# ProPrj_HSSM-Prog_2025-06-12.net
KiCad netlist of a schematic drawn in EasyEDA Pro
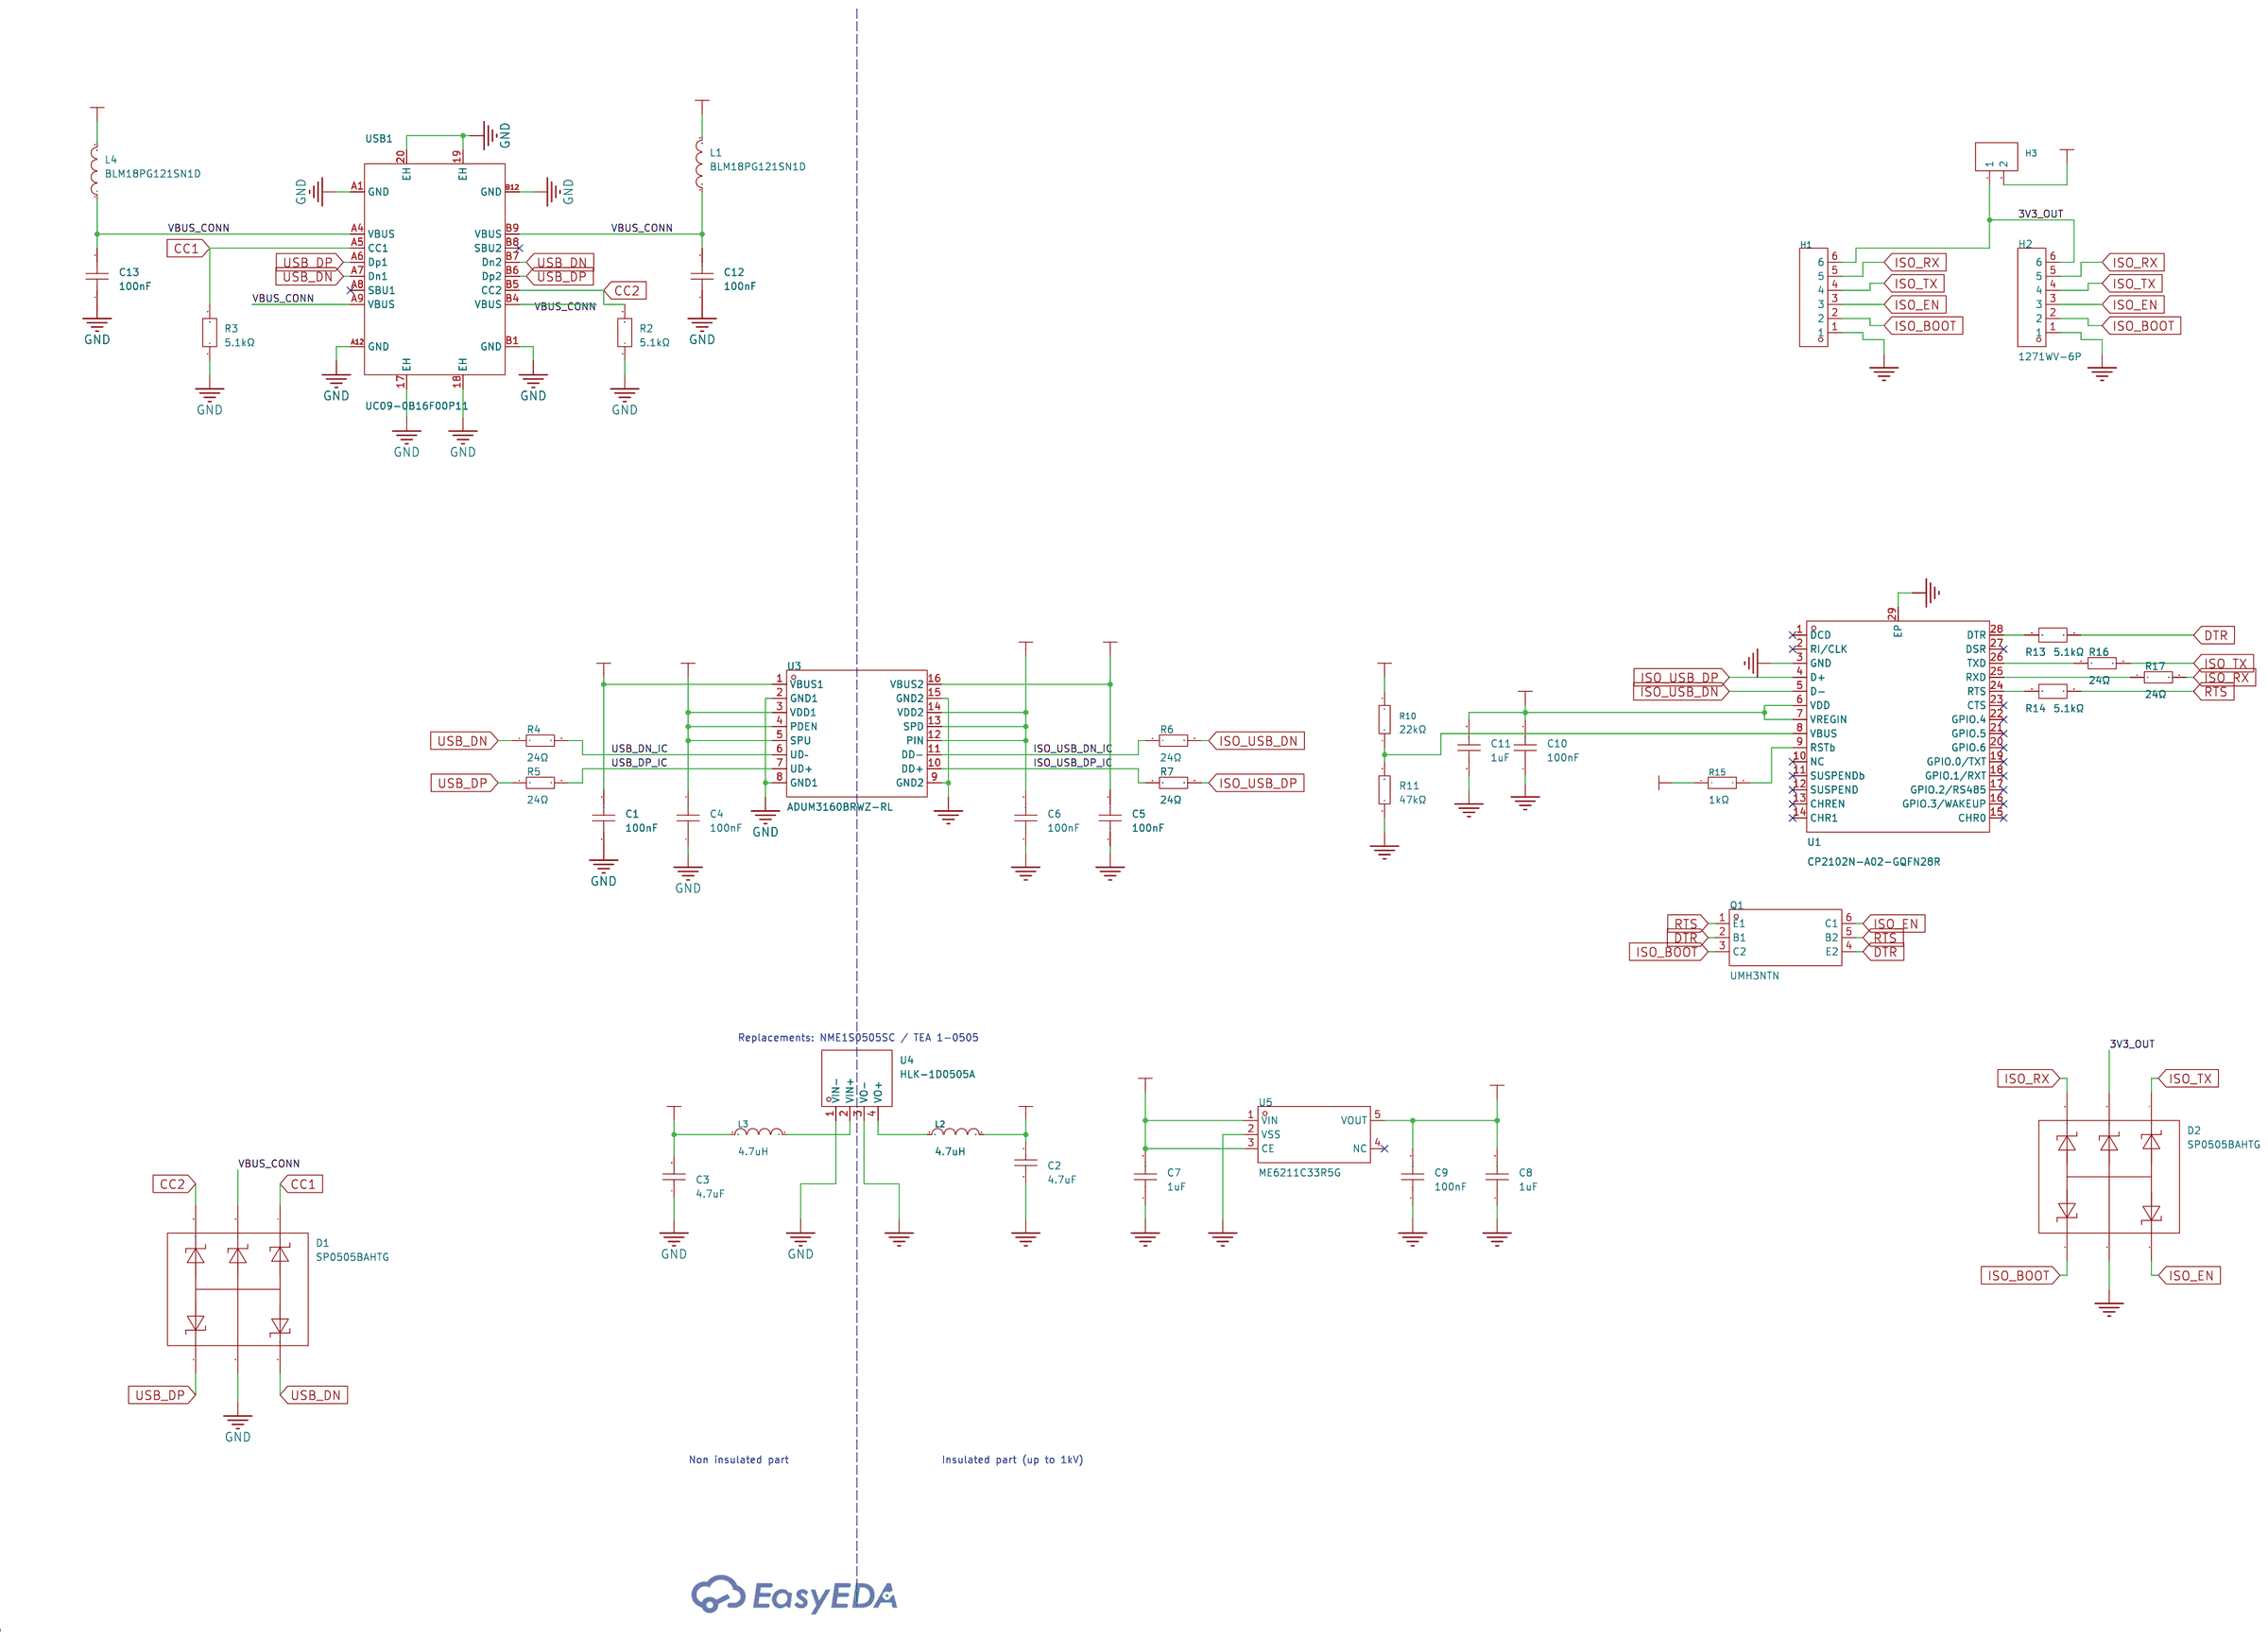
[diagram p0: schematic sheet]

(export (version "E")
  (design (tool "Eeschema 10.0.6"))
  (components
    (comp (ref "C1")
      (value "100nF")
      (footprint "easyedapro:C0402")
      (fields
        (field (name "Manufacturer Part") "CL05B104KO5NNNC")
        (field (name "Manufacturer") "SAMSUNG(三星)")
      )
      (libsource (lib "easyedapro") (part "CL05B104KO5NNNC"))
    )
    (comp (ref "C2")
      (value "4.7uF")
      (footprint "easyedapro:C0603")
      (fields
        (field (name "Manufacturer Part") "CL10A475KO8NNNC")
        (field (name "Manufacturer") "SAMSUNG(三星)")
      )
      (libsource (lib "easyedapro") (part "CL10A475KO8NNNC"))
    )
    (comp (ref "C3")
      (value "4.7uF")
      (footprint "easyedapro:C0603")
      (fields
        (field (name "Manufacturer Part") "CL10A475KO8NNNC")
        (field (name "Manufacturer") "SAMSUNG(三星)")
      )
      (libsource (lib "easyedapro") (part "CL10A475KO8NNNC"))
    )
    (comp (ref "C4")
      (value "100nF")
      (footprint "easyedapro:C0402")
      (fields
        (field (name "Manufacturer Part") "CL05B104KO5NNNC")
        (field (name "Manufacturer") "SAMSUNG(三星)")
      )
      (libsource (lib "easyedapro") (part "CL05B104KO5NNNC"))
    )
    (comp (ref "C5")
      (value "100nF")
      (footprint "easyedapro:C0402")
      (fields
        (field (name "Manufacturer Part") "CL05B104KO5NNNC")
        (field (name "Manufacturer") "SAMSUNG(三星)")
      )
      (libsource (lib "easyedapro") (part "CL05B104KO5NNNC"))
    )
    (comp (ref "C6")
      (value "100nF")
      (footprint "easyedapro:C0402")
      (fields
        (field (name "Manufacturer Part") "CL05B104KO5NNNC")
        (field (name "Manufacturer") "SAMSUNG(三星)")
      )
      (libsource (lib "easyedapro") (part "CL05B104KO5NNNC"))
    )
    (comp (ref "C7")
      (value "1uF")
      (footprint "easyedapro:C0402")
      (fields
        (field (name "Manufacturer Part") "CL05A105KA5NQNC")
        (field (name "Manufacturer") "SAMSUNG(三星)")
      )
      (libsource (lib "easyedapro") (part "CL05A105KA5NQNC"))
    )
    (comp (ref "C8")
      (value "1uF")
      (footprint "easyedapro:C0402")
      (fields
        (field (name "Manufacturer Part") "CL05A105KA5NQNC")
        (field (name "Manufacturer") "SAMSUNG(三星)")
      )
      (libsource (lib "easyedapro") (part "CL05A105KA5NQNC"))
    )
    (comp (ref "C9")
      (value "100nF")
      (footprint "easyedapro:C0402")
      (fields
        (field (name "Manufacturer Part") "CL05B104KO5NNNC")
        (field (name "Manufacturer") "SAMSUNG(三星)")
      )
      (libsource (lib "easyedapro") (part "CL05B104KO5NNNC"))
    )
    (comp (ref "C10")
      (value "100nF")
      (footprint "easyedapro:C0402")
      (fields
        (field (name "Manufacturer Part") "CL05B104KO5NNNC")
        (field (name "Manufacturer") "SAMSUNG(三星)")
      )
      (libsource (lib "easyedapro") (part "CL05B104KO5NNNC"))
    )
    (comp (ref "C11")
      (value "1uF")
      (footprint "easyedapro:C0402")
      (fields
        (field (name "Manufacturer Part") "CL05A105KA5NQNC")
        (field (name "Manufacturer") "SAMSUNG(三星)")
      )
      (libsource (lib "easyedapro") (part "CL05A105KA5NQNC"))
    )
    (comp (ref "C12")
      (value "100nF")
      (footprint "easyedapro:C0402")
      (fields
        (field (name "Manufacturer Part") "CL05B104KO5NNNC")
        (field (name "Manufacturer") "SAMSUNG(三星)")
      )
      (libsource (lib "easyedapro") (part "CL05B104KO5NNNC"))
    )
    (comp (ref "C13")
      (value "100nF")
      (footprint "easyedapro:C0402")
      (fields
        (field (name "Manufacturer Part") "CL05B104KO5NNNC")
        (field (name "Manufacturer") "SAMSUNG(三星)")
      )
      (libsource (lib "easyedapro") (part "CL05B104KO5NNNC"))
    )
    (comp (ref "D1")
      (value "SP0505BAHTG")
      (footprint "easyedapro:SOT-23-6_L2.9-W1.6-P0.95-LS2.8-BR")
      (fields (field (name "Manufacturer") "Littelfuse(美国力特)"))
      (libsource (lib "easyedapro") (part "SP0505BAHTG"))
    )
    (comp (ref "D2")
      (value "SP0505BAHTG")
      (footprint "easyedapro:SOT-23-6_L2.9-W1.6-P0.95-LS2.8-BR")
      (fields (field (name "Manufacturer") "Littelfuse(美国力特)"))
      (libsource (lib "easyedapro") (part "SP0505BAHTG"))
    )
    (comp (ref "H1")
      (value "~")
      (footprint "easyedapro:HDR-TH_6P-P2.54-V-F")
      (libsource (lib "easyedapro") (part "Header-Female-2.54_1x6"))
    )
    (comp (ref "H2")
      (value "1271WV-6P")
      (footprint "easyedapro:HDR-TH_6P-P1.27-V-M-A")
      (fields (field (name "Manufacturer") "HanElectricity(瀚源)"))
      (libsource (lib "easyedapro") (part "1271WV-6P"))
    )
    (comp (ref "H3")
      (value "~")
      (footprint "easyedapro:HDR-TH_2P-P2.54-V-F")
      (libsource (lib "easyedapro") (part "Header-Female-2.54_1x2"))
    )
    (comp (ref "L1")
      (value "BLM18PG121SN1D")
      (footprint "easyedapro:L0603")
      (fields (field (name "Manufacturer") "muRata(村田)"))
      (libsource (lib "easyedapro") (part "BLM18PG121SN1D_C14709"))
    )
    (comp (ref "L2")
      (value "4.7uH")
      (footprint "easyedapro:IND-SMD_L4.0-W4.0_SMNR4020")
      (fields (field (name "Manufacturer Part") "FNR4012S4R7MT") (field (name "Manufacturer") "cjiang(长江微电)"))
      (libsource (lib "easyedapro") (part "FNR4012S4R7MT"))
    )
    (comp (ref "L3")
      (value "4.7uH")
      (footprint "easyedapro:IND-SMD_L4.0-W4.0_SMNR4020")
      (fields (field (name "Manufacturer Part") "FNR4012S4R7MT") (field (name "Manufacturer") "cjiang(长江微电)"))
      (libsource (lib "easyedapro") (part "FNR4012S4R7MT"))
    )
    (comp (ref "L4")
      (value "BLM18PG121SN1D")
      (footprint "easyedapro:L0603")
      (fields (field (name "Manufacturer") "muRata(村田)"))
      (libsource (lib "easyedapro") (part "BLM18PG121SN1D_C14709"))
    )
    (comp (ref "Q1")
      (value "UMH3NTN")
      (footprint "easyedapro:SOT-363_L2.0-W1.3-P0.65-LS2.1-TL")
      (fields (field (name "Manufacturer") "ROHM(罗姆)"))
      (libsource (lib "easyedapro") (part "UMH3NTN"))
    )
    (comp (ref "R2")
      (value "5.1kΩ")
      (footprint "easyedapro:R0402")
      (fields (field (name "Manufacturer Part") "RCA025K1JLF") (field (name "Manufacturer") "HKR(香港电阻)"))
      (libsource (lib "easyedapro") (part "RCA025K1JLF"))
    )
    (comp (ref "R3")
      (value "5.1kΩ")
      (footprint "easyedapro:R0402")
      (fields (field (name "Manufacturer Part") "RCA025K1JLF") (field (name "Manufacturer") "HKR(香港电阻)"))
      (libsource (lib "easyedapro") (part "RCA025K1JLF"))
    )
    (comp (ref "R4")
      (value "24Ω")
      (footprint "easyedapro:R0402")
      (fields (field (name "Manufacturer Part") "AC0402FR-0724RL") (field (name "Manufacturer") "YAGEO(国巨)"))
      (libsource (lib "easyedapro") (part "AC0402FR-0724RL"))
    )
    (comp (ref "R5")
      (value "24Ω")
      (footprint "easyedapro:R0402")
      (fields (field (name "Manufacturer Part") "AC0402FR-0724RL") (field (name "Manufacturer") "YAGEO(国巨)"))
      (libsource (lib "easyedapro") (part "AC0402FR-0724RL"))
    )
    (comp (ref "R6")
      (value "24Ω")
      (footprint "easyedapro:R0402")
      (fields (field (name "Manufacturer Part") "AC0402FR-0724RL") (field (name "Manufacturer") "YAGEO(国巨)"))
      (libsource (lib "easyedapro") (part "AC0402FR-0724RL"))
    )
    (comp (ref "R7")
      (value "24Ω")
      (footprint "easyedapro:R0402")
      (fields (field (name "Manufacturer Part") "AC0402FR-0724RL") (field (name "Manufacturer") "YAGEO(国巨)"))
      (libsource (lib "easyedapro") (part "AC0402FR-0724RL"))
    )
    (comp (ref "R10")
      (value "22kΩ")
      (footprint "easyedapro:R0402")
      (fields
        (field (name "Manufacturer Part") "0402WGF2202TCE")
        (field (name "Manufacturer") "UNI-ROYAL(厚声)")
      )
      (libsource (lib "easyedapro") (part "0402WGF2202TCE"))
    )
    (comp (ref "R11")
      (value "47kΩ")
      (footprint "easyedapro:R0402")
      (fields
        (field (name "Manufacturer Part") "0402WGF4702TCE")
        (field (name "Manufacturer") "UNI-ROYAL(厚声)")
      )
      (libsource (lib "easyedapro") (part "0402WGF4702TCE"))
    )
    (comp (ref "R13")
      (value "5.1kΩ")
      (footprint "easyedapro:R0402")
      (fields (field (name "Manufacturer Part") "RCA025K1JLF") (field (name "Manufacturer") "HKR(香港电阻)"))
      (libsource (lib "easyedapro") (part "RCA025K1JLF"))
    )
    (comp (ref "R14")
      (value "5.1kΩ")
      (footprint "easyedapro:R0402")
      (fields (field (name "Manufacturer Part") "RCA025K1JLF") (field (name "Manufacturer") "HKR(香港电阻)"))
      (libsource (lib "easyedapro") (part "RCA025K1JLF"))
    )
    (comp (ref "R15")
      (value "1kΩ")
      (footprint "easyedapro:R0402")
      (fields
        (field (name "Manufacturer Part") "0402WGF1001TCE")
        (field (name "Manufacturer") "UNI-ROYAL(厚声)")
      )
      (libsource (lib "easyedapro") (part "0402WGF1001TCE"))
    )
    (comp (ref "R16")
      (value "24Ω")
      (footprint "easyedapro:R0402")
      (fields (field (name "Manufacturer Part") "AC0402FR-0724RL") (field (name "Manufacturer") "YAGEO(国巨)"))
      (libsource (lib "easyedapro") (part "AC0402FR-0724RL"))
    )
    (comp (ref "R17")
      (value "24Ω")
      (footprint "easyedapro:R0402")
      (fields (field (name "Manufacturer Part") "AC0402FR-0724RL") (field (name "Manufacturer") "YAGEO(国巨)"))
      (libsource (lib "easyedapro") (part "AC0402FR-0724RL"))
    )
    (comp (ref "U1")
      (value "CP2102N-A02-GQFN28R")
      (footprint "easyedapro:QFN-28_L5.0-W5.0-P0.50-TL-EP3.3")
      (fields (field (name "Manufacturer") "SKYWORKS/SILICON LABS(芯科)"))
      (libsource (lib "easyedapro") (part "CP2102N-A02-GQFN28R"))
    )
    (comp (ref "U3")
      (value "ADUM3160BRWZ-RL")
      (footprint "easyedapro:SOIC-16_L10.3-W7.5-P1.27-LS10.3-BL")
      (fields (field (name "Manufacturer") "ADI(亚德诺)"))
      (libsource (lib "easyedapro") (part "ADUM3160BRWZ-RL"))
    )
    (comp (ref "U4")
      (value "HLK-1D0505A")
      (footprint "easyedapro:PWRM-TH_HLK-1DXXXX")
      (fields (field (name "Manufacturer") "HI-LINK(海凌科)"))
      (libsource (lib "easyedapro") (part "HLK-1D0505A"))
    )
    (comp (ref "U5")
      (value "ME6211C33R5G")
      (footprint "easyedapro:SOT-353_L2.1-W1.3-P0.65-LS2.3-BL")
      (fields (field (name "Manufacturer") "MICRONE(南京微盟)"))
      (libsource (lib "easyedapro") (part "ME6211C33R5G"))
    )
    (comp (ref "USB1")
      (value "UC09-0B16F00P11")
      (footprint "easyedapro:USB-C_UC09-0B16F00P11")
      (fields (field (name "Manufacturer") "BXCONN(宝讯)"))
      (libsource (lib "easyedapro") (part "UC09-0B16F00P11"))
    )
  )
  (nets
    (net (code "1") (name "/3V3_OUT") (class "Default")
      (node (ref "D2") (pin "5") (pinfunction "5_5") (pintype "input"))
      (node (ref "H1") (pin "6") (pinfunction "6_6") (pintype "input"))
      (node (ref "H2") (pin "6") (pinfunction "6_6") (pintype "unspecified"))
      (node (ref "H3") (pin "1") (pinfunction "1_1") (pintype "input"))
    )
    (net (code "2") (name "/ISO_USB_DN_IC") (class "Default")
      (node (ref "R6") (pin "1") (pinfunction "1_1") (pintype "unspecified"))
      (node (ref "U3") (pin "11") (pinfunction "DD-_11") (pintype "unspecified"))
    )
    (net (code "3") (name "/ISO_USB_DP_IC") (class "Default")
      (node (ref "R7") (pin "1") (pinfunction "1_1") (pintype "unspecified"))
      (node (ref "U3") (pin "10") (pinfunction "DD+_10") (pintype "unspecified"))
    )
    (net (code "4") (name "/USB_DN_IC") (class "Default")
      (node (ref "R4") (pin "2") (pinfunction "2_2") (pintype "unspecified"))
      (node (ref "U3") (pin "6") (pinfunction "UD–_6") (pintype "unspecified"))
    )
    (net (code "5") (name "/USB_DP_IC") (class "Default")
      (node (ref "R5") (pin "2") (pinfunction "2_2") (pintype "unspecified"))
      (node (ref "U3") (pin "7") (pinfunction "UD+_7") (pintype "unspecified"))
    )
    (net (code "6") (name "/VBUS_CONN") (class "Default")
      (node (ref "C12") (pin "2") (pinfunction "2_2") (pintype "unspecified"))
      (node (ref "C13") (pin "2") (pinfunction "2_2") (pintype "unspecified"))
      (node (ref "D1") (pin "5") (pinfunction "5_5") (pintype "input"))
      (node (ref "L1") (pin "1") (pinfunction "1_1") (pintype "unspecified"))
      (node (ref "L4") (pin "1") (pinfunction "1_1") (pintype "unspecified"))
      (node (ref "USB1") (pin "A4") (pinfunction "VBUS_A4") (pintype "unspecified"))
      (node (ref "USB1") (pin "A9") (pinfunction "VBUS_A9") (pintype "unspecified"))
      (node (ref "USB1") (pin "B4") (pinfunction "VBUS_B4") (pintype "unspecified"))
      (node (ref "USB1") (pin "B9") (pinfunction "VBUS_B9") (pintype "unspecified"))
    )
    (net (code "7") (name "CC1") (class "Default")
      (node (ref "D1") (pin "4") (pinfunction "4_4") (pintype "input"))
      (node (ref "R3") (pin "2") (pinfunction "2_2") (pintype "unspecified"))
      (node (ref "USB1") (pin "A5") (pinfunction "CC1_A5") (pintype "unspecified"))
    )
    (net (code "8") (name "CC2") (class "Default")
      (node (ref "D1") (pin "6") (pinfunction "6_6") (pintype "input"))
      (node (ref "R2") (pin "2") (pinfunction "2_2") (pintype "unspecified"))
      (node (ref "USB1") (pin "B5") (pinfunction "CC2_B5") (pintype "unspecified"))
    )
    (net (code "9") (name "DTR") (class "Default")
      (node (ref "Q1") (pin "2") (pinfunction "B1_2") (pintype "unspecified"))
      (node (ref "Q1") (pin "4") (pinfunction "E2_4") (pintype "unspecified"))
      (node (ref "R13") (pin "1") (pinfunction "1_1") (pintype "unspecified"))
    )
    (net (code "10") (name "GND") (class "Default")
      (node (ref "C1") (pin "1") (pinfunction "1_1") (pintype "unspecified"))
      (node (ref "C12") (pin "1") (pinfunction "1_1") (pintype "unspecified"))
      (node (ref "C13") (pin "1") (pinfunction "1_1") (pintype "unspecified"))
      (node (ref "C3") (pin "1") (pinfunction "1_1") (pintype "input"))
      (node (ref "C4") (pin "1") (pinfunction "1_1") (pintype "unspecified"))
      (node (ref "D1") (pin "2") (pinfunction "2_2") (pintype "input"))
      (node (ref "R2") (pin "1") (pinfunction "1_1") (pintype "unspecified"))
      (node (ref "R3") (pin "1") (pinfunction "1_1") (pintype "unspecified"))
      (node (ref "U3") (pin "2") (pinfunction "GND1_2") (pintype "unspecified"))
      (node (ref "U3") (pin "8") (pinfunction "GND1_8") (pintype "unspecified"))
      (node (ref "U4") (pin "1") (pinfunction "VIN-_1") (pintype "unspecified"))
      (node (ref "USB1") (pin "17") (pinfunction "EH_17") (pintype "unspecified"))
      (node (ref "USB1") (pin "18") (pinfunction "EH_18") (pintype "unspecified"))
      (node (ref "USB1") (pin "19") (pinfunction "EH_19") (pintype "unspecified"))
      (node (ref "USB1") (pin "20") (pinfunction "EH_20") (pintype "unspecified"))
      (node (ref "USB1") (pin "A1") (pinfunction "GND_A1") (pintype "unspecified"))
      (node (ref "USB1") (pin "A12") (pinfunction "GND_A12") (pintype "unspecified"))
      (node (ref "USB1") (pin "B1") (pinfunction "GND_B1") (pintype "unspecified"))
      (node (ref "USB1") (pin "B12") (pinfunction "GND_B12") (pintype "unspecified"))
    )
    (net (code "11") (name "ISO3V3") (class "Default")
      (node (ref "C10") (pin "2") (pinfunction "2_2") (pintype "unspecified"))
      (node (ref "C11") (pin "2") (pinfunction "2_2") (pintype "unspecified"))
      (node (ref "C8") (pin "2") (pinfunction "2_2") (pintype "unspecified"))
      (node (ref "C9") (pin "2") (pinfunction "2_2") (pintype "unspecified"))
      (node (ref "H3") (pin "2") (pinfunction "2_2") (pintype "input"))
      (node (ref "R15") (pin "1") (pinfunction "1_1") (pintype "input"))
      (node (ref "U1") (pin "6") (pinfunction "VDD_6") (pintype "unspecified"))
      (node (ref "U1") (pin "7") (pinfunction "VREGIN_7") (pintype "unspecified"))
      (node (ref "U5") (pin "5") (pinfunction "VOUT_5") (pintype "input"))
    )
    (net (code "12") (name "ISOGND") (class "Default")
      (node (ref "C10") (pin "1") (pinfunction "1_1") (pintype "unspecified"))
      (node (ref "C11") (pin "1") (pinfunction "1_1") (pintype "unspecified"))
      (node (ref "C2") (pin "1") (pinfunction "1_1") (pintype "input"))
      (node (ref "C5") (pin "1") (pinfunction "1_1") (pintype "unspecified"))
      (node (ref "C6") (pin "1") (pinfunction "1_1") (pintype "unspecified"))
      (node (ref "C7") (pin "1") (pinfunction "1_1") (pintype "unspecified"))
      (node (ref "C8") (pin "1") (pinfunction "1_1") (pintype "unspecified"))
      (node (ref "C9") (pin "1") (pinfunction "1_1") (pintype "unspecified"))
      (node (ref "D2") (pin "2") (pinfunction "2_2") (pintype "input"))
      (node (ref "H1") (pin "1") (pinfunction "1_1") (pintype "input"))
      (node (ref "H2") (pin "1") (pinfunction "1_1") (pintype "unspecified"))
      (node (ref "R11") (pin "1") (pinfunction "1_1") (pintype "input"))
      (node (ref "U1") (pin "29") (pinfunction "EP_29") (pintype "unspecified"))
      (node (ref "U1") (pin "3") (pinfunction "GND_3") (pintype "unspecified"))
      (node (ref "U3") (pin "15") (pinfunction "GND2_15") (pintype "unspecified"))
      (node (ref "U3") (pin "9") (pinfunction "GND2_9") (pintype "unspecified"))
      (node (ref "U4") (pin "3") (pinfunction "VO-_3") (pintype "unspecified"))
      (node (ref "U5") (pin "2") (pinfunction "VSS_2") (pintype "input"))
    )
    (net (code "13") (name "ISOVBUS") (class "Default")
      (node (ref "C2") (pin "2") (pinfunction "2_2") (pintype "input"))
      (node (ref "C5") (pin "2") (pinfunction "2_2") (pintype "unspecified"))
      (node (ref "C7") (pin "2") (pinfunction "2_2") (pintype "unspecified"))
      (node (ref "L2") (pin "1") (pinfunction "1_1") (pintype "input"))
      (node (ref "R10") (pin "2") (pinfunction "2_2") (pintype "input"))
      (node (ref "U3") (pin "16") (pinfunction "VBUS2_16") (pintype "unspecified"))
      (node (ref "U5") (pin "1") (pinfunction "VIN_1") (pintype "input"))
      (node (ref "U5") (pin "3") (pinfunction "CE_3") (pintype "input"))
    )
    (net (code "14") (name "ISOVDD") (class "Default")
      (node (ref "C6") (pin "2") (pinfunction "2_2") (pintype "unspecified"))
      (node (ref "U3") (pin "12") (pinfunction "PIN_12") (pintype "unspecified"))
      (node (ref "U3") (pin "13") (pinfunction "SPD_13") (pintype "unspecified"))
      (node (ref "U3") (pin "14") (pinfunction "VDD2_14") (pintype "unspecified"))
    )
    (net (code "15") (name "ISO_BOOT") (class "Default")
      (node (ref "D2") (pin "1") (pinfunction "1_1") (pintype "input"))
      (node (ref "H1") (pin "2") (pinfunction "2_2") (pintype "input"))
      (node (ref "H2") (pin "2") (pinfunction "2_2") (pintype "unspecified"))
      (node (ref "Q1") (pin "3") (pinfunction "C2_3") (pintype "unspecified"))
    )
    (net (code "16") (name "ISO_EN") (class "Default")
      (node (ref "D2") (pin "3") (pinfunction "3_3") (pintype "input"))
      (node (ref "H1") (pin "3") (pinfunction "3_3") (pintype "input"))
      (node (ref "H2") (pin "3") (pinfunction "3_3") (pintype "unspecified"))
      (node (ref "Q1") (pin "6") (pinfunction "C1_6") (pintype "unspecified"))
    )
    (net (code "17") (name "ISO_RX") (class "Default")
      (node (ref "D2") (pin "6") (pinfunction "6_6") (pintype "input"))
      (node (ref "H1") (pin "5") (pinfunction "5_5") (pintype "input"))
      (node (ref "H2") (pin "5") (pinfunction "5_5") (pintype "unspecified"))
      (node (ref "R17") (pin "2") (pinfunction "2_2") (pintype "unspecified"))
    )
    (net (code "18") (name "ISO_TX") (class "Default")
      (node (ref "D2") (pin "4") (pinfunction "4_4") (pintype "input"))
      (node (ref "H1") (pin "4") (pinfunction "4_4") (pintype "input"))
      (node (ref "H2") (pin "4") (pinfunction "4_4") (pintype "unspecified"))
      (node (ref "R16") (pin "2") (pinfunction "2_2") (pintype "unspecified"))
    )
    (net (code "19") (name "ISO_USB_DN") (class "Default")
      (node (ref "R6") (pin "2") (pinfunction "2_2") (pintype "unspecified"))
      (node (ref "U1") (pin "5") (pinfunction "D-_5") (pintype "unspecified"))
    )
    (net (code "20") (name "ISO_USB_DP") (class "Default")
      (node (ref "R7") (pin "2") (pinfunction "2_2") (pintype "unspecified"))
      (node (ref "U1") (pin "4") (pinfunction "D+_4") (pintype "unspecified"))
    )
    (net (code "21") (name "Net-(U1-DTR)") (class "Default")
      (node (ref "R13") (pin "2") (pinfunction "2_2") (pintype "unspecified"))
      (node (ref "U1") (pin "28") (pinfunction "DTR_28") (pintype "unspecified"))
    )
    (net (code "22") (name "Net-(U1-RSTb)") (class "Default")
      (node (ref "R15") (pin "2") (pinfunction "2_2") (pintype "input"))
      (node (ref "U1") (pin "9") (pinfunction "RSTb_9") (pintype "unspecified"))
    )
    (net (code "23") (name "Net-(U1-RTS)") (class "Default")
      (node (ref "R14") (pin "2") (pinfunction "2_2") (pintype "unspecified"))
      (node (ref "U1") (pin "24") (pinfunction "RTS_24") (pintype "unspecified"))
    )
    (net (code "24") (name "Net-(U1-RXD)") (class "Default")
      (node (ref "R17") (pin "1") (pinfunction "1_1") (pintype "unspecified"))
      (node (ref "U1") (pin "25") (pinfunction "RXD_25") (pintype "unspecified"))
    )
    (net (code "25") (name "Net-(U1-TXD)") (class "Default")
      (node (ref "R16") (pin "1") (pinfunction "1_1") (pintype "unspecified"))
      (node (ref "U1") (pin "26") (pinfunction "TXD_26") (pintype "unspecified"))
    )
    (net (code "26") (name "Net-(U1-VBUS)") (class "Default")
      (node (ref "R10") (pin "1") (pinfunction "1_1") (pintype "input"))
      (node (ref "R11") (pin "2") (pinfunction "2_2") (pintype "input"))
      (node (ref "U1") (pin "8") (pinfunction "VBUS_8") (pintype "unspecified"))
    )
    (net (code "27") (name "Net-(U4-VIN+)") (class "Default")
      (node (ref "L3") (pin "1") (pinfunction "1_1") (pintype "input"))
      (node (ref "U4") (pin "2") (pinfunction "VIN+_2") (pintype "unspecified"))
    )
    (net (code "28") (name "Net-(U4-VO+)") (class "Default")
      (node (ref "L2") (pin "2") (pinfunction "2_2") (pintype "input"))
      (node (ref "U4") (pin "4") (pinfunction "VO+_4") (pintype "unspecified"))
    )
    (net (code "29") (name "RTS") (class "Default")
      (node (ref "Q1") (pin "1") (pinfunction "E1_1") (pintype "unspecified"))
      (node (ref "Q1") (pin "5") (pinfunction "B2_5") (pintype "unspecified"))
      (node (ref "R14") (pin "1") (pinfunction "1_1") (pintype "unspecified"))
    )
    (net (code "30") (name "USB_DN") (class "Default")
      (node (ref "D1") (pin "3") (pinfunction "3_3") (pintype "input"))
      (node (ref "R4") (pin "1") (pinfunction "1_1") (pintype "unspecified"))
      (node (ref "USB1") (pin "A7") (pinfunction "Dn1_A7") (pintype "unspecified"))
      (node (ref "USB1") (pin "B7") (pinfunction "Dn2_B7") (pintype "unspecified"))
    )
    (net (code "31") (name "USB_DP") (class "Default")
      (node (ref "D1") (pin "1") (pinfunction "1_1") (pintype "input"))
      (node (ref "R5") (pin "1") (pinfunction "1_1") (pintype "unspecified"))
      (node (ref "USB1") (pin "A6") (pinfunction "Dp1_A6") (pintype "unspecified"))
      (node (ref "USB1") (pin "B6") (pinfunction "Dp2_B6") (pintype "unspecified"))
    )
    (net (code "32") (name "VBUS") (class "Default")
      (node (ref "C1") (pin "2") (pinfunction "2_2") (pintype "unspecified"))
      (node (ref "C3") (pin "2") (pinfunction "2_2") (pintype "input"))
      (node (ref "L1") (pin "2") (pinfunction "2_2") (pintype "unspecified"))
      (node (ref "L3") (pin "2") (pinfunction "2_2") (pintype "input"))
      (node (ref "L4") (pin "2") (pinfunction "2_2") (pintype "unspecified"))
      (node (ref "U3") (pin "1") (pinfunction "VBUS1_1") (pintype "unspecified"))
    )
    (net (code "33") (name "VDD") (class "Default")
      (node (ref "C4") (pin "2") (pinfunction "2_2") (pintype "unspecified"))
      (node (ref "U3") (pin "3") (pinfunction "VDD1_3") (pintype "unspecified"))
      (node (ref "U3") (pin "4") (pinfunction "PDEN_4") (pintype "unspecified"))
      (node (ref "U3") (pin "5") (pinfunction "SPU_5") (pintype "unspecified"))
    )
    (net (code "34") (name "unconnected-(U1-CHR0-Pad15)") (class "Default")
      (node (ref "U1") (pin "15") (pinfunction "CHR0_15") (pintype "unspecified+no_connect"))
    )
    (net (code "35") (name "unconnected-(U1-CHR1-Pad14)") (class "Default")
      (node (ref "U1") (pin "14") (pinfunction "CHR1_14") (pintype "unspecified+no_connect"))
    )
    (net (code "36") (name "unconnected-(U1-CHREN-Pad13)") (class "Default")
      (node (ref "U1") (pin "13") (pinfunction "CHREN_13") (pintype "unspecified+no_connect"))
    )
    (net (code "37") (name "unconnected-(U1-CTS-Pad23)") (class "Default")
      (node (ref "U1") (pin "23") (pinfunction "CTS_23") (pintype "unspecified+no_connect"))
    )
    (net (code "38") (name "unconnected-(U1-DCD-Pad1)") (class "Default")
      (node (ref "U1") (pin "1") (pinfunction "DCD_1") (pintype "unspecified+no_connect"))
    )
    (net (code "39") (name "unconnected-(U1-DSR-Pad27)") (class "Default")
      (node (ref "U1") (pin "27") (pinfunction "DSR_27") (pintype "unspecified+no_connect"))
    )
    (net (code "40") (name "unconnected-(U1-GPIO.0{slash}TXT-Pad19)") (class "Default")
      (node (ref "U1") (pin "19") (pinfunction "GPIO.0/TXT_19") (pintype "unspecified+no_connect"))
    )
    (net (code "41") (name "unconnected-(U1-GPIO.1{slash}RXT-Pad18)") (class "Default")
      (node (ref "U1") (pin "18") (pinfunction "GPIO.1/RXT_18") (pintype "unspecified+no_connect"))
    )
    (net (code "42") (name "unconnected-(U1-GPIO.2{slash}RS485-Pad17)") (class "Default")
      (node (ref "U1") (pin "17") (pinfunction "GPIO.2/RS485_17") (pintype "unspecified+no_connect"))
    )
    (net (code "43") (name "unconnected-(U1-GPIO.3{slash}WAKEUP-Pad16)") (class "Default")
      (node (ref "U1") (pin "16") (pinfunction "GPIO.3/WAKEUP_16") (pintype "unspecified+no_connect"))
    )
    (net (code "44") (name "unconnected-(U1-GPIO.4-Pad22)") (class "Default")
      (node (ref "U1") (pin "22") (pinfunction "GPIO.4_22") (pintype "unspecified+no_connect"))
    )
    (net (code "45") (name "unconnected-(U1-GPIO.5-Pad21)") (class "Default")
      (node (ref "U1") (pin "21") (pinfunction "GPIO.5_21") (pintype "unspecified+no_connect"))
    )
    (net (code "46") (name "unconnected-(U1-GPIO.6-Pad20)") (class "Default")
      (node (ref "U1") (pin "20") (pinfunction "GPIO.6_20") (pintype "unspecified+no_connect"))
    )
    (net (code "47") (name "unconnected-(U1-NC-Pad10)") (class "Default")
      (node (ref "U1") (pin "10") (pinfunction "NC_10") (pintype "unspecified+no_connect"))
    )
    (net (code "48") (name "unconnected-(U1-RI{slash}CLK-Pad2)") (class "Default")
      (node (ref "U1") (pin "2") (pinfunction "RI/CLK_2") (pintype "unspecified+no_connect"))
    )
    (net (code "49") (name "unconnected-(U1-SUSPEND-Pad12)") (class "Default")
      (node (ref "U1") (pin "12") (pinfunction "SUSPEND_12") (pintype "unspecified+no_connect"))
    )
    (net (code "50") (name "unconnected-(U1-SUSPENDb-Pad11)") (class "Default")
      (node (ref "U1") (pin "11") (pinfunction "SUSPENDb_11") (pintype "unspecified+no_connect"))
    )
    (net (code "51") (name "unconnected-(U5-NC-Pad4)") (class "Default")
      (node (ref "U5") (pin "4") (pinfunction "NC_4") (pintype "input+no_connect"))
    )
    (net (code "52") (name "unconnected-(USB1-SBU1-PadA8)") (class "Default")
      (node (ref "USB1") (pin "A8") (pinfunction "SBU1_A8") (pintype "unspecified+no_connect"))
    )
    (net (code "53") (name "unconnected-(USB1-SBU2-PadB8)") (class "Default")
      (node (ref "USB1") (pin "B8") (pinfunction "SBU2_B8") (pintype "unspecified+no_connect"))
    )
  )
)
